# Adafruit_Terminal_PiCowbell_for_Pico.net
KiCad netlist of a schematic drawn in EAGLE
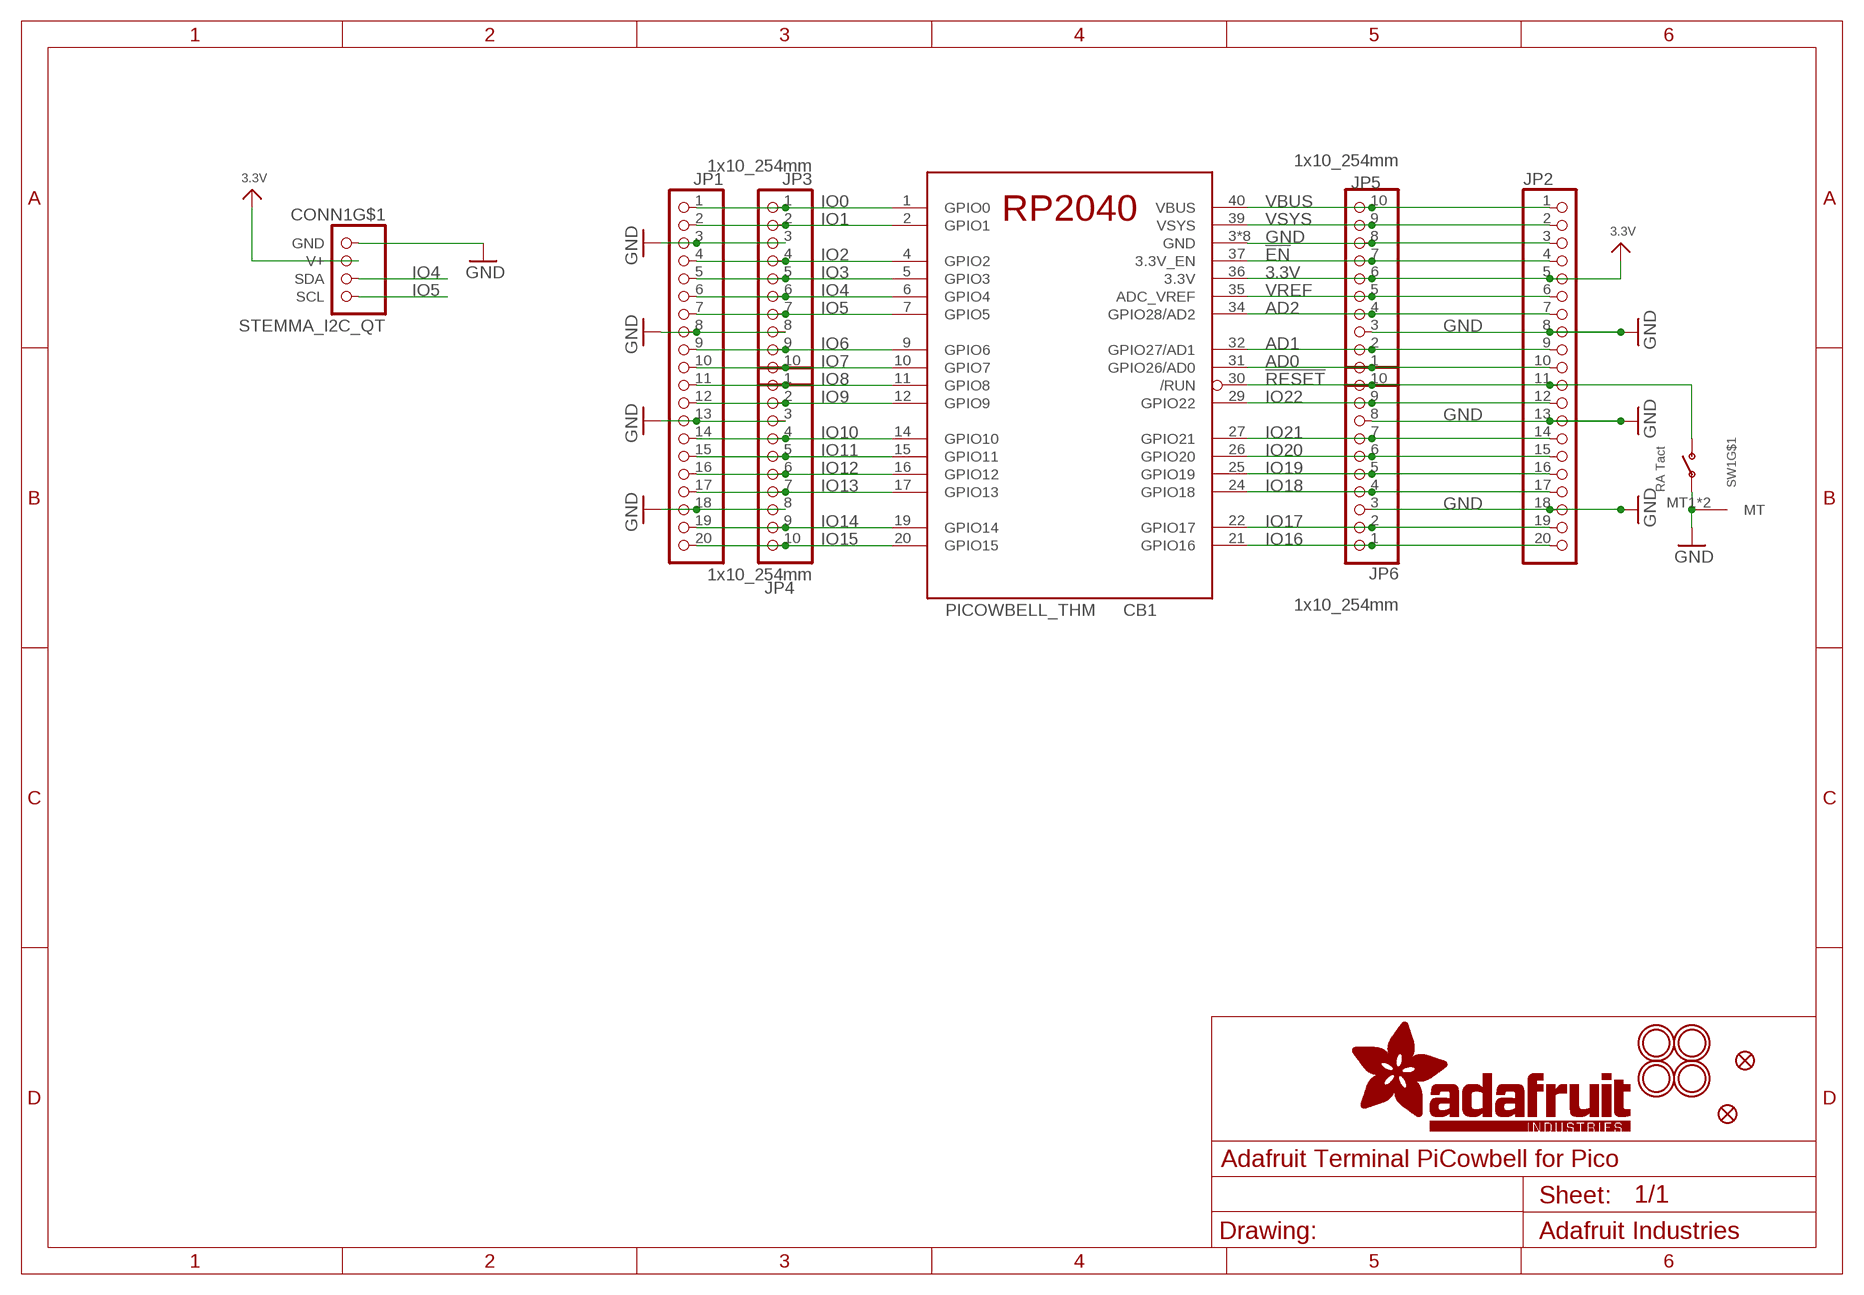
[diagram p0: schematic, sheet 1]

(export (version "E")
  (design (tool "Eeschema 10.0.6"))
  (components
    (comp (ref "CB1")
      (value "PICOWBELL_THM")
      (footprint "eagle-import:PICOWBELL_THM")
      (libsource (lib "eagle-import") (part "PICOWBELL_THM"))
    )
    (comp (ref "CONN1")
      (value "STEMMA_I2C_QT")
      (footprint "eagle-import:JST_SH4")
      (libsource (lib "eagle-import") (part "STEMMA_I2C_QT"))
    )
    (comp (ref "FID1")
      (value "FIDUCIAL_1MM")
      (footprint "eagle-import:FIDUCIAL_1MM")
      (libsource (lib "eagle-import") (part "FIDUCIAL_1MM"))
    )
    (comp (ref "FID2")
      (value "FIDUCIAL_1MM")
      (footprint "eagle-import:FIDUCIAL_1MM")
      (libsource (lib "eagle-import") (part "FIDUCIAL_1MM"))
    )
    (comp (ref "JP1")
      (value "HEADER-1X20_70MIL")
      (footprint "eagle-import:1X20_ROUND_70MIL")
      (libsource (lib "eagle-import") (part "HEADER-1X20_70MIL"))
    )
    (comp (ref "JP2")
      (value "HEADER-1X20_70MIL")
      (footprint "eagle-import:1X20_ROUND_70MIL")
      (libsource (lib "eagle-import") (part "HEADER-1X20_70MIL"))
    )
    (comp (ref "JP3")
      (value "1x10_254mm")
      (footprint "eagle-import:1X10_2.54MMTERMINAL")
      (libsource (lib "eagle-import") (part "HEADER-1X10_254MM_TERM"))
    )
    (comp (ref "JP4")
      (value "1x10_254mm")
      (footprint "eagle-import:1X10_2.54MMTERMINAL")
      (libsource (lib "eagle-import") (part "HEADER-1X10_254MM_TERM"))
    )
    (comp (ref "JP5")
      (value "1x10_254mm")
      (footprint "eagle-import:1X10_2.54MMTERMINAL")
      (libsource (lib "eagle-import") (part "HEADER-1X10_254MM_TERM"))
    )
    (comp (ref "JP6")
      (value "1x10_254mm")
      (footprint "eagle-import:1X10_2.54MMTERMINAL")
      (libsource (lib "eagle-import") (part "HEADER-1X10_254MM_TERM"))
    )
    (comp (ref "SW1")
      (value "RA Tact")
      (footprint "eagle-import:SPST_TACTILE_RA")
      (libsource (lib "eagle-import") (part "SWITCH_SPST_MNT_TACT_RA"))
    )
    (comp (ref "U$5")
      (value "MOUNTINGHOLE3.0THIN")
      (footprint "eagle-import:MOUNTINGHOLE_3.0_PLATEDTHIN")
      (libsource (lib "eagle-import") (part "MOUNTINGHOLE3.0THIN"))
    )
    (comp (ref "U$7")
      (value "MOUNTINGHOLE3.0THIN")
      (footprint "eagle-import:MOUNTINGHOLE_3.0_PLATEDTHIN")
      (libsource (lib "eagle-import") (part "MOUNTINGHOLE3.0THIN"))
    )
    (comp (ref "U$8")
      (value "MOUNTINGHOLE3.0THIN")
      (footprint "eagle-import:MOUNTINGHOLE_3.0_PLATEDTHIN")
      (libsource (lib "eagle-import") (part "MOUNTINGHOLE3.0THIN"))
    )
    (comp (ref "U$9")
      (value "MOUNTINGHOLE3.0THIN")
      (footprint "eagle-import:MOUNTINGHOLE_3.0_PLATEDTHIN")
      (libsource (lib "eagle-import") (part "MOUNTINGHOLE3.0THIN"))
    )
  )
  (nets
    (net (code "1") (name "/AD0") (class "Default")
      (node (ref "CB1") (pin "31") (pinfunction "GPIO26/AD0_31") (pintype "bidirectional"))
      (node (ref "JP2") (pin "10") (pinfunction "10_10") (pintype "passive"))
      (node (ref "JP5") (pin "1") (pinfunction "1_1") (pintype "passive"))
    )
    (net (code "2") (name "/AD1") (class "Default")
      (node (ref "CB1") (pin "32") (pinfunction "GPIO27/AD1_32") (pintype "bidirectional"))
      (node (ref "JP2") (pin "9") (pinfunction "9_9") (pintype "passive"))
      (node (ref "JP5") (pin "2") (pinfunction "2_2") (pintype "passive"))
    )
    (net (code "3") (name "/AD2") (class "Default")
      (node (ref "CB1") (pin "34") (pinfunction "GPIO28/AD2_34") (pintype "bidirectional"))
      (node (ref "JP2") (pin "7") (pinfunction "7_7") (pintype "passive"))
      (node (ref "JP5") (pin "4") (pinfunction "4_4") (pintype "passive"))
    )
    (net (code "4") (name "/IO0") (class "Default")
      (node (ref "CB1") (pin "1") (pinfunction "GPIO0_1") (pintype "bidirectional"))
      (node (ref "JP1") (pin "1") (pinfunction "1_1") (pintype "passive"))
      (node (ref "JP3") (pin "1") (pinfunction "1_1") (pintype "passive"))
    )
    (net (code "5") (name "/IO1") (class "Default")
      (node (ref "CB1") (pin "2") (pinfunction "GPIO1_2") (pintype "bidirectional"))
      (node (ref "JP1") (pin "2") (pinfunction "2_2") (pintype "passive"))
      (node (ref "JP3") (pin "2") (pinfunction "2_2") (pintype "passive"))
    )
    (net (code "6") (name "/IO2") (class "Default")
      (node (ref "CB1") (pin "4") (pinfunction "GPIO2_4") (pintype "bidirectional"))
      (node (ref "JP1") (pin "4") (pinfunction "4_4") (pintype "passive"))
      (node (ref "JP3") (pin "4") (pinfunction "4_4") (pintype "passive"))
    )
    (net (code "7") (name "/IO3") (class "Default")
      (node (ref "CB1") (pin "5") (pinfunction "GPIO3_5") (pintype "bidirectional"))
      (node (ref "JP1") (pin "5") (pinfunction "5_5") (pintype "passive"))
      (node (ref "JP3") (pin "5") (pinfunction "5_5") (pintype "passive"))
    )
    (net (code "8") (name "/IO4") (class "Default")
      (node (ref "CB1") (pin "6") (pinfunction "GPIO4_6") (pintype "bidirectional"))
      (node (ref "CONN1") (pin "3") (pinfunction "SDA_3") (pintype "passive"))
      (node (ref "JP1") (pin "6") (pinfunction "6_6") (pintype "passive"))
      (node (ref "JP3") (pin "6") (pinfunction "6_6") (pintype "passive"))
    )
    (net (code "9") (name "/IO5") (class "Default")
      (node (ref "CB1") (pin "7") (pinfunction "GPIO5_7") (pintype "bidirectional"))
      (node (ref "CONN1") (pin "4") (pinfunction "SCL_4") (pintype "passive"))
      (node (ref "JP1") (pin "7") (pinfunction "7_7") (pintype "passive"))
      (node (ref "JP3") (pin "7") (pinfunction "7_7") (pintype "passive"))
    )
    (net (code "10") (name "/IO6") (class "Default")
      (node (ref "CB1") (pin "9") (pinfunction "GPIO6_9") (pintype "bidirectional"))
      (node (ref "JP1") (pin "9") (pinfunction "9_9") (pintype "passive"))
      (node (ref "JP3") (pin "9") (pinfunction "9_9") (pintype "passive"))
    )
    (net (code "11") (name "/IO7") (class "Default")
      (node (ref "CB1") (pin "10") (pinfunction "GPIO7_10") (pintype "bidirectional"))
      (node (ref "JP1") (pin "10") (pinfunction "10_10") (pintype "passive"))
      (node (ref "JP3") (pin "10") (pinfunction "10_10") (pintype "passive"))
    )
    (net (code "12") (name "/IO8") (class "Default")
      (node (ref "CB1") (pin "11") (pinfunction "GPIO8_11") (pintype "bidirectional"))
      (node (ref "JP1") (pin "11") (pinfunction "11_11") (pintype "passive"))
      (node (ref "JP4") (pin "1") (pinfunction "1_1") (pintype "passive"))
    )
    (net (code "13") (name "/IO9") (class "Default")
      (node (ref "CB1") (pin "12") (pinfunction "GPIO9_12") (pintype "bidirectional"))
      (node (ref "JP1") (pin "12") (pinfunction "12_12") (pintype "passive"))
      (node (ref "JP4") (pin "2") (pinfunction "2_2") (pintype "passive"))
    )
    (net (code "14") (name "/IO10") (class "Default")
      (node (ref "CB1") (pin "14") (pinfunction "GPIO10_14") (pintype "bidirectional"))
      (node (ref "JP1") (pin "14") (pinfunction "14_14") (pintype "passive"))
      (node (ref "JP4") (pin "4") (pinfunction "4_4") (pintype "passive"))
    )
    (net (code "15") (name "/IO11") (class "Default")
      (node (ref "CB1") (pin "15") (pinfunction "GPIO11_15") (pintype "bidirectional"))
      (node (ref "JP1") (pin "15") (pinfunction "15_15") (pintype "passive"))
      (node (ref "JP4") (pin "5") (pinfunction "5_5") (pintype "passive"))
    )
    (net (code "16") (name "/IO12") (class "Default")
      (node (ref "CB1") (pin "16") (pinfunction "GPIO12_16") (pintype "bidirectional"))
      (node (ref "JP1") (pin "16") (pinfunction "16_16") (pintype "passive"))
      (node (ref "JP4") (pin "6") (pinfunction "6_6") (pintype "passive"))
    )
    (net (code "17") (name "/IO13") (class "Default")
      (node (ref "CB1") (pin "17") (pinfunction "GPIO13_17") (pintype "bidirectional"))
      (node (ref "JP1") (pin "17") (pinfunction "17_17") (pintype "passive"))
      (node (ref "JP4") (pin "7") (pinfunction "7_7") (pintype "passive"))
    )
    (net (code "18") (name "/IO14") (class "Default")
      (node (ref "CB1") (pin "19") (pinfunction "GPIO14_19") (pintype "bidirectional"))
      (node (ref "JP1") (pin "19") (pinfunction "19_19") (pintype "passive"))
      (node (ref "JP4") (pin "9") (pinfunction "9_9") (pintype "passive"))
    )
    (net (code "19") (name "/IO15") (class "Default")
      (node (ref "CB1") (pin "20") (pinfunction "GPIO15_20") (pintype "bidirectional"))
      (node (ref "JP1") (pin "20") (pinfunction "20_20") (pintype "passive"))
      (node (ref "JP4") (pin "10") (pinfunction "10_10") (pintype "passive"))
    )
    (net (code "20") (name "/IO16") (class "Default")
      (node (ref "CB1") (pin "21") (pinfunction "GPIO16_21") (pintype "bidirectional"))
      (node (ref "JP2") (pin "20") (pinfunction "20_20") (pintype "passive"))
      (node (ref "JP6") (pin "1") (pinfunction "1_1") (pintype "passive"))
    )
    (net (code "21") (name "/IO17") (class "Default")
      (node (ref "CB1") (pin "22") (pinfunction "GPIO17_22") (pintype "bidirectional"))
      (node (ref "JP2") (pin "19") (pinfunction "19_19") (pintype "passive"))
      (node (ref "JP6") (pin "2") (pinfunction "2_2") (pintype "passive"))
    )
    (net (code "22") (name "/IO18") (class "Default")
      (node (ref "CB1") (pin "24") (pinfunction "GPIO18_24") (pintype "bidirectional"))
      (node (ref "JP2") (pin "17") (pinfunction "17_17") (pintype "passive"))
      (node (ref "JP6") (pin "4") (pinfunction "4_4") (pintype "passive"))
    )
    (net (code "23") (name "/IO19") (class "Default")
      (node (ref "CB1") (pin "25") (pinfunction "GPIO19_25") (pintype "bidirectional"))
      (node (ref "JP2") (pin "16") (pinfunction "16_16") (pintype "passive"))
      (node (ref "JP6") (pin "5") (pinfunction "5_5") (pintype "passive"))
    )
    (net (code "24") (name "/IO20") (class "Default")
      (node (ref "CB1") (pin "26") (pinfunction "GPIO20_26") (pintype "bidirectional"))
      (node (ref "JP2") (pin "15") (pinfunction "15_15") (pintype "passive"))
      (node (ref "JP6") (pin "6") (pinfunction "6_6") (pintype "passive"))
    )
    (net (code "25") (name "/IO21") (class "Default")
      (node (ref "CB1") (pin "27") (pinfunction "GPIO21_27") (pintype "bidirectional"))
      (node (ref "JP2") (pin "14") (pinfunction "14_14") (pintype "passive"))
      (node (ref "JP6") (pin "7") (pinfunction "7_7") (pintype "passive"))
    )
    (net (code "26") (name "/IO22") (class "Default")
      (node (ref "CB1") (pin "29") (pinfunction "GPIO22_29") (pintype "bidirectional"))
      (node (ref "JP2") (pin "12") (pinfunction "12_12") (pintype "passive"))
      (node (ref "JP6") (pin "9") (pinfunction "9_9") (pintype "passive"))
    )
    (net (code "27") (name "/VBUS") (class "Default")
      (node (ref "CB1") (pin "40") (pinfunction "VBUS_40") (pintype "power_in"))
      (node (ref "JP2") (pin "1") (pinfunction "1_1") (pintype "passive"))
      (node (ref "JP5") (pin "10") (pinfunction "10_10") (pintype "passive"))
    )
    (net (code "28") (name "/VREF") (class "Default")
      (node (ref "CB1") (pin "35") (pinfunction "ADC_VREF_35") (pintype "passive"))
      (node (ref "JP2") (pin "6") (pinfunction "6_6") (pintype "passive"))
      (node (ref "JP5") (pin "5") (pinfunction "5_5") (pintype "passive"))
    )
    (net (code "29") (name "/VSYS") (class "Default")
      (node (ref "CB1") (pin "39") (pinfunction "VSYS_39") (pintype "power_in"))
      (node (ref "JP2") (pin "2") (pinfunction "2_2") (pintype "passive"))
      (node (ref "JP5") (pin "9") (pinfunction "9_9") (pintype "passive"))
    )
    (net (code "30") (name "/~{EN}") (class "Default")
      (node (ref "CB1") (pin "37") (pinfunction "3.3V_EN_37") (pintype "passive"))
      (node (ref "JP2") (pin "4") (pinfunction "4_4") (pintype "passive"))
      (node (ref "JP5") (pin "7") (pinfunction "7_7") (pintype "passive"))
    )
    (net (code "31") (name "/~{RESET}") (class "Default")
      (node (ref "CB1") (pin "30") (pinfunction "/RUN_30") (pintype "bidirectional"))
      (node (ref "JP2") (pin "11") (pinfunction "11_11") (pintype "passive"))
      (node (ref "JP6") (pin "10") (pinfunction "10_10") (pintype "passive"))
      (node (ref "SW1") (pin "2") (pinfunction "S_2") (pintype "passive"))
    )
    (net (code "32") (name "3.3V") (class "Default")
      (node (ref "CB1") (pin "36") (pinfunction "3.3V_36") (pintype "power_in"))
      (node (ref "CONN1") (pin "2") (pinfunction "V+_2") (pintype "passive"))
      (node (ref "JP2") (pin "5") (pinfunction "5_5") (pintype "passive"))
      (node (ref "JP5") (pin "6") (pinfunction "6_6") (pintype "passive"))
    )
    (net (code "33") (name "GND") (class "Default")
      (node (ref "CB1") (pin "13") (pinfunction "GND_13") (pintype "power_in"))
      (node (ref "CB1") (pin "18") (pinfunction "GND_18") (pintype "power_in"))
      (node (ref "CB1") (pin "23") (pinfunction "GND_23") (pintype "power_in"))
      (node (ref "CB1") (pin "28") (pinfunction "GND_28") (pintype "power_in"))
      (node (ref "CB1") (pin "3") (pinfunction "GND_3") (pintype "power_in"))
      (node (ref "CB1") (pin "33") (pinfunction "GND_33") (pintype "power_in"))
      (node (ref "CB1") (pin "38") (pinfunction "GND_38") (pintype "power_in"))
      (node (ref "CB1") (pin "8") (pinfunction "GND_8") (pintype "power_in"))
      (node (ref "CONN1") (pin "1") (pinfunction "GND_1") (pintype "passive"))
      (node (ref "JP1") (pin "13") (pinfunction "13_13") (pintype "passive"))
      (node (ref "JP1") (pin "18") (pinfunction "18_18") (pintype "passive"))
      (node (ref "JP1") (pin "3") (pinfunction "3_3") (pintype "passive"))
      (node (ref "JP1") (pin "8") (pinfunction "8_8") (pintype "passive"))
      (node (ref "JP2") (pin "13") (pinfunction "13_13") (pintype "passive"))
      (node (ref "JP2") (pin "18") (pinfunction "18_18") (pintype "passive"))
      (node (ref "JP2") (pin "3") (pinfunction "3_3") (pintype "passive"))
      (node (ref "JP2") (pin "8") (pinfunction "8_8") (pintype "passive"))
      (node (ref "JP3") (pin "3") (pinfunction "3_3") (pintype "passive"))
      (node (ref "JP3") (pin "8") (pinfunction "8_8") (pintype "passive"))
      (node (ref "JP4") (pin "3") (pinfunction "3_3") (pintype "passive"))
      (node (ref "JP4") (pin "8") (pinfunction "8_8") (pintype "passive"))
      (node (ref "JP5") (pin "3") (pinfunction "3_3") (pintype "passive"))
      (node (ref "JP5") (pin "8") (pinfunction "8_8") (pintype "passive"))
      (node (ref "JP6") (pin "3") (pinfunction "3_3") (pintype "passive"))
      (node (ref "JP6") (pin "8") (pinfunction "8_8") (pintype "passive"))
      (node (ref "SW1") (pin "1") (pinfunction "P_1") (pintype "passive"))
      (node (ref "SW1") (pin "MT1") (pinfunction "MT_MT1") (pintype "bidirectional"))
      (node (ref "SW1") (pin "MT2") (pinfunction "MT_MT2") (pintype "bidirectional"))
    )
  )
)
